# hhv-dcdarknet-varient-1.net
KiCad netlist of a schematic drawn in EAGLE
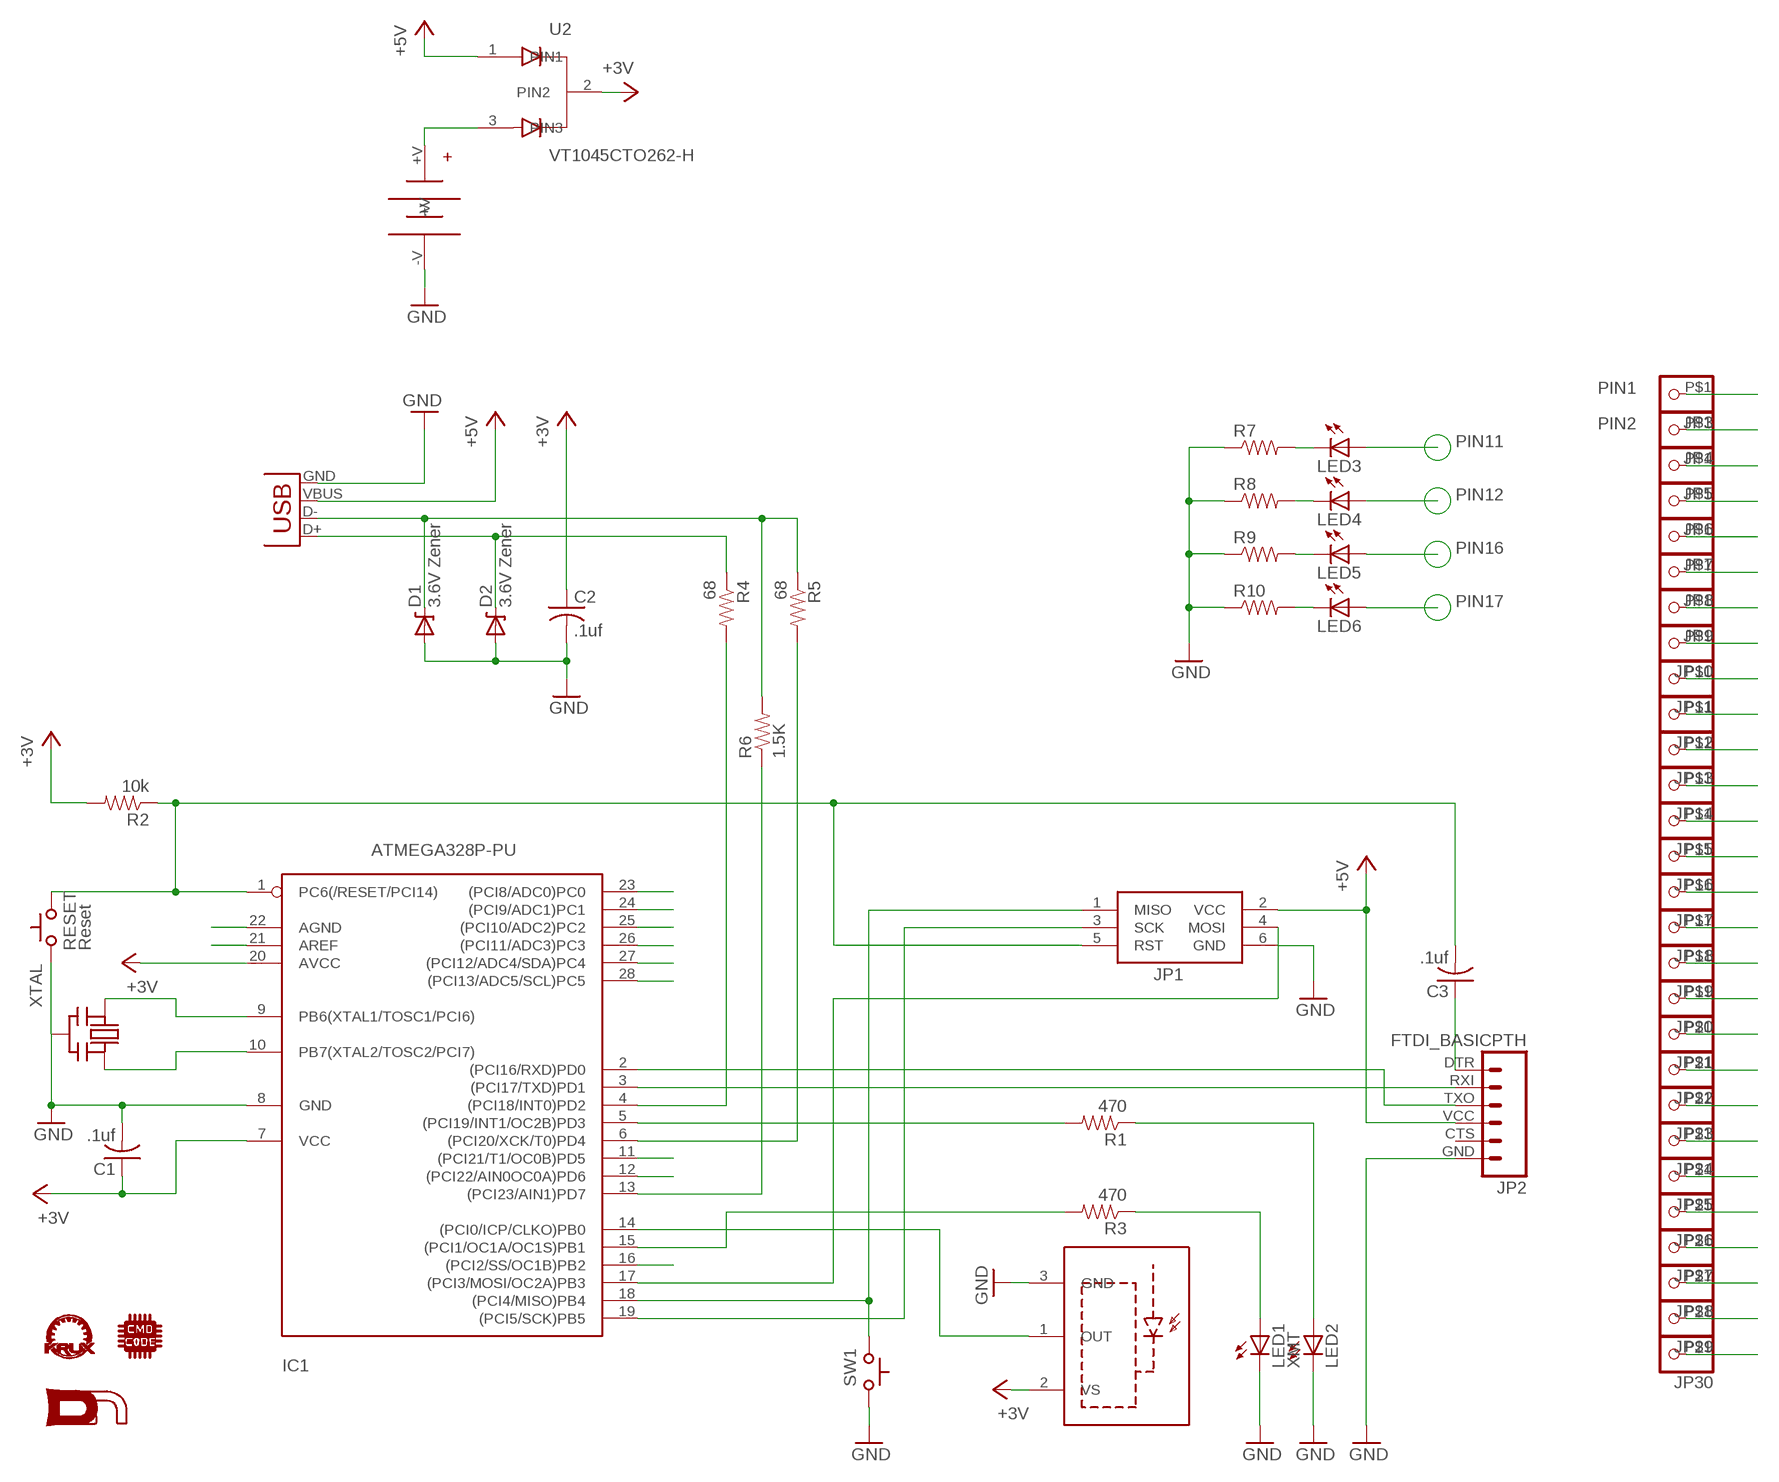
[diagram p0: schematic, sheet 1]

(export (version "E")
  (design (tool "Eeschema 10.0.6"))
  (components
    (comp (ref "C1")
      (value ".1uf")
      (footprint "eagle-import:C025-030X050")
      (libsource (lib "eagle-import") (part "C-US025-030X050"))
    )
    (comp (ref "C2")
      (value ".1uf")
      (footprint "eagle-import:C025-030X050")
      (libsource (lib "eagle-import") (part "C-US025-030X050"))
    )
    (comp (ref "C3")
      (value ".1uf")
      (footprint "eagle-import:C025-030X050")
      (libsource (lib "eagle-import") (part "C-US025-030X050"))
    )
    (comp (ref "D1")
      (value "3.6V Zener")
      (footprint "eagle-import:DIODE-ZENER")
      (libsource (lib "eagle-import") (part "DIODE-ZENERPTH"))
    )
    (comp (ref "D2")
      (value "3.6V Zener")
      (footprint "eagle-import:DIODE-ZENER")
      (libsource (lib "eagle-import") (part "DIODE-ZENERPTH"))
    )
    (comp (ref "IC1")
      (value "ATMEGA328P-PU")
      (footprint "eagle-import:DIL28-3")
      (libsource (lib "eagle-import") (part "ATMEGA168PV-10"))
    )
    (comp (ref "JP1")
      (value "JP1")
      (footprint "eagle-import:AVRISP")
      (libsource (lib "eagle-import") (part "AVRISP-6"))
    )
    (comp (ref "JP2")
      (value "FTDI_BASICPTH")
      (footprint "eagle-import:FTDI_BASIC")
      (libsource (lib "eagle-import") (part "FTDI_BASICPTH"))
    )
    (comp (ref "JP3")
      (value "PINHD-1X11X1_SQUARE")
      (footprint "eagle-import:1X1-SMALL_CUT")
      (libsource (lib "eagle-import") (part "PINHD-1X11X1_SQUARE"))
    )
    (comp (ref "JP4")
      (value "PINHD-1X11X1_SQUARE")
      (footprint "eagle-import:1X1-SMALL_CUT")
      (libsource (lib "eagle-import") (part "PINHD-1X11X1_SQUARE"))
    )
    (comp (ref "JP5")
      (value "PINHD-1X11X1_SQUARE")
      (footprint "eagle-import:1X1-SMALL_CUT")
      (libsource (lib "eagle-import") (part "PINHD-1X11X1_SQUARE"))
    )
    (comp (ref "JP6")
      (value "PINHD-1X11X1_SQUARE")
      (footprint "eagle-import:1X1-SMALL_CUT")
      (libsource (lib "eagle-import") (part "PINHD-1X11X1_SQUARE"))
    )
    (comp (ref "JP7")
      (value "PINHD-1X11X1_SQUARE")
      (footprint "eagle-import:1X1-SMALL_CUT")
      (libsource (lib "eagle-import") (part "PINHD-1X11X1_SQUARE"))
    )
    (comp (ref "JP8")
      (value "PINHD-1X11X1_SQUARE")
      (footprint "eagle-import:1X1-SMALL_CUT")
      (libsource (lib "eagle-import") (part "PINHD-1X11X1_SQUARE"))
    )
    (comp (ref "JP9")
      (value "PINHD-1X11X1_SQUARE")
      (footprint "eagle-import:1X1-SMALL_CUT")
      (libsource (lib "eagle-import") (part "PINHD-1X11X1_SQUARE"))
    )
    (comp (ref "JP10")
      (value "PINHD-1X11X1_SQUARE")
      (footprint "eagle-import:1X1-SMALL_CUT")
      (libsource (lib "eagle-import") (part "PINHD-1X11X1_SQUARE"))
    )
    (comp (ref "JP11")
      (value "PINHD-1X11X1_SQUARE")
      (footprint "eagle-import:1X1-SMALL_CUT")
      (libsource (lib "eagle-import") (part "PINHD-1X11X1_SQUARE"))
    )
    (comp (ref "JP12")
      (value "PINHD-1X11X1_SQUARE")
      (footprint "eagle-import:1X1-SMALL_CUT")
      (libsource (lib "eagle-import") (part "PINHD-1X11X1_SQUARE"))
    )
    (comp (ref "JP13")
      (value "PINHD-1X11X1_SQUARE")
      (footprint "eagle-import:1X1-SMALL_CUT")
      (libsource (lib "eagle-import") (part "PINHD-1X11X1_SQUARE"))
    )
    (comp (ref "JP14")
      (value "PINHD-1X11X1_SQUARE")
      (footprint "eagle-import:1X1-SMALL_CUT")
      (libsource (lib "eagle-import") (part "PINHD-1X11X1_SQUARE"))
    )
    (comp (ref "JP15")
      (value "PINHD-1X11X1_SQUARE")
      (footprint "eagle-import:1X1-SMALL_CUT")
      (libsource (lib "eagle-import") (part "PINHD-1X11X1_SQUARE"))
    )
    (comp (ref "JP16")
      (value "PINHD-1X11X1_SQUARE")
      (footprint "eagle-import:1X1-SMALL_CUT")
      (libsource (lib "eagle-import") (part "PINHD-1X11X1_SQUARE"))
    )
    (comp (ref "JP17")
      (value "PINHD-1X11X1_SQUARE")
      (footprint "eagle-import:1X1-SMALL_CUT")
      (libsource (lib "eagle-import") (part "PINHD-1X11X1_SQUARE"))
    )
    (comp (ref "JP18")
      (value "PINHD-1X11X1_SQUARE")
      (footprint "eagle-import:1X1-SMALL_CUT")
      (libsource (lib "eagle-import") (part "PINHD-1X11X1_SQUARE"))
    )
    (comp (ref "JP19")
      (value "PINHD-1X11X1_SQUARE")
      (footprint "eagle-import:1X1-SMALL_CUT")
      (libsource (lib "eagle-import") (part "PINHD-1X11X1_SQUARE"))
    )
    (comp (ref "JP20")
      (value "PINHD-1X11X1_SQUARE")
      (footprint "eagle-import:1X1-SMALL_CUT")
      (libsource (lib "eagle-import") (part "PINHD-1X11X1_SQUARE"))
    )
    (comp (ref "JP21")
      (value "PINHD-1X11X1_SQUARE")
      (footprint "eagle-import:1X1-SMALL_CUT")
      (libsource (lib "eagle-import") (part "PINHD-1X11X1_SQUARE"))
    )
    (comp (ref "JP22")
      (value "PINHD-1X11X1_SQUARE")
      (footprint "eagle-import:1X1-SMALL_CUT")
      (libsource (lib "eagle-import") (part "PINHD-1X11X1_SQUARE"))
    )
    (comp (ref "JP23")
      (value "PINHD-1X11X1_SQUARE")
      (footprint "eagle-import:1X1-SMALL_CUT")
      (libsource (lib "eagle-import") (part "PINHD-1X11X1_SQUARE"))
    )
    (comp (ref "JP24")
      (value "PINHD-1X11X1_SQUARE")
      (footprint "eagle-import:1X1-SMALL_CUT")
      (libsource (lib "eagle-import") (part "PINHD-1X11X1_SQUARE"))
    )
    (comp (ref "JP25")
      (value "PINHD-1X11X1_SQUARE")
      (footprint "eagle-import:1X1-SMALL_CUT")
      (libsource (lib "eagle-import") (part "PINHD-1X11X1_SQUARE"))
    )
    (comp (ref "JP26")
      (value "PINHD-1X11X1_SQUARE")
      (footprint "eagle-import:1X1-SMALL_CUT")
      (libsource (lib "eagle-import") (part "PINHD-1X11X1_SQUARE"))
    )
    (comp (ref "JP27")
      (value "PINHD-1X11X1_SQUARE")
      (footprint "eagle-import:1X1-SMALL_CUT")
      (libsource (lib "eagle-import") (part "PINHD-1X11X1_SQUARE"))
    )
    (comp (ref "JP28")
      (value "PINHD-1X11X1_SQUARE")
      (footprint "eagle-import:1X1-SMALL_CUT")
      (libsource (lib "eagle-import") (part "PINHD-1X11X1_SQUARE"))
    )
    (comp (ref "JP29")
      (value "PINHD-1X11X1-SMALL")
      (footprint "eagle-import:1X1-SMALL")
      (libsource (lib "eagle-import") (part "PINHD-1X11X1-SMALL"))
    )
    (comp (ref "JP30")
      (value "PINHD-1X11X1-SMALL")
      (footprint "eagle-import:1X1-SMALL")
      (libsource (lib "eagle-import") (part "PINHD-1X11X1-SMALL"))
    )
    (comp (ref "LED1")
      (value "XMT")
      (footprint "eagle-import:LED5MM-FLAT")
      (libsource (lib "eagle-import") (part "LED5MM-FLAT"))
    )
    (comp (ref "LED2")
      (value "LED5MM-FLAT")
      (footprint "eagle-import:LED5MM-FLAT")
      (libsource (lib "eagle-import") (part "LED5MM-FLAT"))
    )
    (comp (ref "LED3")
      (value "LED1206")
      (footprint "eagle-import:LED-1206")
      (libsource (lib "eagle-import") (part "SparkFun_LED1206"))
    )
    (comp (ref "LED4")
      (value "LED1206")
      (footprint "eagle-import:LED-1206")
      (libsource (lib "eagle-import") (part "SparkFun_LED1206"))
    )
    (comp (ref "LED5")
      (value "LED1206")
      (footprint "eagle-import:LED-1206")
      (libsource (lib "eagle-import") (part "SparkFun_LED1206"))
    )
    (comp (ref "LED6")
      (value "LED1206")
      (footprint "eagle-import:LED-1206")
      (libsource (lib "eagle-import") (part "SparkFun_LED1206"))
    )
    (comp (ref "R1")
      (value "470")
      (footprint "eagle-import:AXIAL-0.3")
      (libsource (lib "eagle-import") (part "RESISTORAXIAL-0.3"))
    )
    (comp (ref "R2")
      (value "10k")
      (footprint "eagle-import:AXIAL-0.3")
      (libsource (lib "eagle-import") (part "RESISTORAXIAL-0.3"))
    )
    (comp (ref "R3")
      (value "470")
      (footprint "eagle-import:AXIAL-0.3")
      (libsource (lib "eagle-import") (part "RESISTORAXIAL-0.3"))
    )
    (comp (ref "R4")
      (value "68")
      (footprint "eagle-import:AXIAL-0.3")
      (libsource (lib "eagle-import") (part "RESISTORAXIAL-0.3"))
    )
    (comp (ref "R5")
      (value "68")
      (footprint "eagle-import:AXIAL-0.3")
      (libsource (lib "eagle-import") (part "RESISTORAXIAL-0.3"))
    )
    (comp (ref "R6")
      (value "1.5K")
      (footprint "eagle-import:AXIAL-0.3")
      (libsource (lib "eagle-import") (part "RESISTORAXIAL-0.3"))
    )
    (comp (ref "R7")
      (value "RESISTOR1206")
      (footprint "eagle-import:1206")
      (libsource (lib "eagle-import") (part "SparkFun_RESISTOR1206"))
    )
    (comp (ref "R8")
      (value "RESISTOR1206")
      (footprint "eagle-import:1206")
      (libsource (lib "eagle-import") (part "SparkFun_RESISTOR1206"))
    )
    (comp (ref "R9")
      (value "RESISTOR1206")
      (footprint "eagle-import:1206")
      (libsource (lib "eagle-import") (part "SparkFun_RESISTOR1206"))
    )
    (comp (ref "R10")
      (value "RESISTOR1206")
      (footprint "eagle-import:1206")
      (libsource (lib "eagle-import") (part "SparkFun_RESISTOR1206"))
    )
    (comp (ref "RESET")
      (value "Reset")
      (footprint "eagle-import:TACTILE-2PIN")
      (libsource (lib "eagle-import") (part "SWITCH_TACTILETACTILE-2PIN"))
    )
    (comp (ref "SW1")
      (value "SWITCH_TACTILETACTILE-2PIN")
      (footprint "eagle-import:TACTILE-2PIN")
      (libsource (lib "eagle-import") (part "SWITCH_TACTILETACTILE-2PIN"))
    )
    (comp (ref "U$1")
      (value "DN_LOGO")
      (footprint "eagle-import:DN_LOGO")
      (libsource (lib "eagle-import") (part "DN_LOGO"))
    )
    (comp (ref "U$2")
      (value "CMDC0DE_LOGO")
      (footprint "eagle-import:CMDC0DE")
      (libsource (lib "eagle-import") (part "CMDC0DE_LOGO"))
    )
    (comp (ref "U$3")
      (value "KRUX_LOGO")
      (footprint "eagle-import:KRUX_LOGO")
      (libsource (lib "eagle-import") (part "KRUX_LOGO"))
    )
    (comp (ref "U$5")
      (value "12BH423-GR3-CELL_NOBORDER")
      (footprint "eagle-import:3-AAA-CELL_NOBORDER")
      (libsource (lib "eagle-import") (part "12BH423-GR3-CELL_NOBORDER"))
    )
    (comp (ref "U1")
      (value "RCV")
      (footprint "eagle-import:IR-MODULE")
      (libsource (lib "eagle-import") (part "SOP22"))
    )
    (comp (ref "U2")
      (value "VT1045CTO262-H")
      (footprint "eagle-import:TO262-H")
      (libsource (lib "eagle-import") (part "VT1045CTO262-H"))
    )
    (comp (ref "X2")
      (value "USB")
      (footprint "eagle-import:USB-B-PTH")
      (libsource (lib "eagle-import") (part "USBPTH"))
    )
    (comp (ref "XTAL")
      (value "CERMOSCILL-THM")
      (footprint "eagle-import:CERM_OSC")
      (libsource (lib "eagle-import") (part "CERMOSCILL-THM"))
    )
  )
  (nets
    (net (code "1") (name "+3V") (class "Default")
      (node (ref "C1") (pin "1") (pinfunction "1_1") (pintype "passive"))
      (node (ref "C2") (pin "1") (pinfunction "1_1") (pintype "passive"))
      (node (ref "IC1") (pin "20") (pinfunction "AVCC_20") (pintype "bidirectional"))
      (node (ref "IC1") (pin "7") (pinfunction "VCC_7") (pintype "bidirectional"))
      (node (ref "JP22") (pin "P$1") (pinfunction "1_P$1") (pintype "passive"))
      (node (ref "JP9") (pin "P$1") (pinfunction "1_P$1") (pintype "passive"))
      (node (ref "R2") (pin "P$2") (pinfunction "2_P$2") (pintype "passive"))
      (node (ref "U1") (pin "2") (pinfunction "VS_2") (pintype "bidirectional"))
      (node (ref "U2") (pin "2") (pinfunction "PIN2_2") (pintype "bidirectional"))
    )
    (net (code "2") (name "+5V") (class "Default")
      (node (ref "JP1") (pin "2") (pinfunction "VCC_2") (pintype "power_in"))
      (node (ref "JP2") (pin "VCC") (pinfunction "4_VCC") (pintype "passive"))
      (node (ref "U2") (pin "1") (pinfunction "PIN1_1") (pintype "bidirectional"))
      (node (ref "X2") (pin "VBUS") (pinfunction "VBUS_VBUS") (pintype "bidirectional"))
    )
    (net (code "3") (name "/PIN1") (class "Default")
      (node (ref "C3") (pin "2") (pinfunction "2_2") (pintype "passive"))
      (node (ref "IC1") (pin "1") (pinfunction "PC6(/RESET/PCI14)_1") (pintype "bidirectional"))
      (node (ref "JP1") (pin "5") (pinfunction "RST_5") (pintype "output"))
      (node (ref "JP3") (pin "P$1") (pinfunction "1_P$1") (pintype "passive"))
      (node (ref "R2") (pin "P$1") (pinfunction "1_P$1") (pintype "passive"))
      (node (ref "RESET") (pin "P$1") (pinfunction "A_P$1") (pintype "passive"))
    )
    (net (code "4") (name "/PIN2") (class "Default")
      (node (ref "IC1") (pin "2") (pinfunction "(PCI16/RXD)PD0_2") (pintype "bidirectional"))
      (node (ref "JP2") (pin "TXO") (pinfunction "3_TXO") (pintype "passive"))
      (node (ref "JP4") (pin "P$1") (pinfunction "1_P$1") (pintype "passive"))
    )
    (net (code "5") (name "/PIN3") (class "Default")
      (node (ref "IC1") (pin "3") (pinfunction "(PCI17/TXD)PD1_3") (pintype "bidirectional"))
      (node (ref "JP2") (pin "RXI") (pinfunction "2_RXI") (pintype "passive"))
      (node (ref "JP5") (pin "P$1") (pinfunction "1_P$1") (pintype "passive"))
    )
    (net (code "6") (name "/PIN4") (class "Default")
      (node (ref "IC1") (pin "4") (pinfunction "(PCI18/INT0)PD2_4") (pintype "bidirectional"))
      (node (ref "JP6") (pin "P$1") (pinfunction "1_P$1") (pintype "passive"))
      (node (ref "R4") (pin "P$2") (pinfunction "2_P$2") (pintype "passive"))
    )
    (net (code "7") (name "/PIN5") (class "Default")
      (node (ref "IC1") (pin "5") (pinfunction "(PCI19/INT1/OC2B)PD3_5") (pintype "bidirectional"))
      (node (ref "JP7") (pin "P$1") (pinfunction "1_P$1") (pintype "passive"))
      (node (ref "R1") (pin "P$2") (pinfunction "2_P$2") (pintype "passive"))
    )
    (net (code "8") (name "/PIN6") (class "Default")
      (node (ref "IC1") (pin "6") (pinfunction "(PCI20/XCK/T0)PD4_6") (pintype "bidirectional"))
      (node (ref "JP8") (pin "P$1") (pinfunction "1_P$1") (pintype "passive"))
      (node (ref "R5") (pin "P$2") (pinfunction "2_P$2") (pintype "passive"))
    )
    (net (code "9") (name "/PIN9") (class "Default")
      (node (ref "IC1") (pin "9") (pinfunction "PB6(XTAL1/TOSC1/PCI6)_9") (pintype "bidirectional"))
      (node (ref "JP11") (pin "P$1") (pinfunction "1_P$1") (pintype "passive"))
      (node (ref "XTAL") (pin "P$1") (pinfunction "IN_P$1") (pintype "bidirectional"))
    )
    (net (code "10") (name "/PIN10") (class "Default")
      (node (ref "IC1") (pin "10") (pinfunction "PB7(XTAL2/TOSC2/PCI7)_10") (pintype "bidirectional"))
      (node (ref "JP12") (pin "P$1") (pinfunction "1_P$1") (pintype "passive"))
      (node (ref "XTAL") (pin "P$3") (pinfunction "OUT_P$3") (pintype "bidirectional"))
    )
    (net (code "11") (name "/PIN11") (class "Default")
      (node (ref "IC1") (pin "11") (pinfunction "(PCI21/T1/OC0B)PD5_11") (pintype "bidirectional"))
      (node (ref "JP13") (pin "P$1") (pinfunction "1_P$1") (pintype "passive"))
      (node (ref "LED3") (pin "A") (pinfunction "A_A") (pintype "passive"))
    )
    (net (code "12") (name "/PIN12") (class "Default")
      (node (ref "IC1") (pin "12") (pinfunction "(PCI22/AIN0OC0A)PD6_12") (pintype "bidirectional"))
      (node (ref "JP14") (pin "P$1") (pinfunction "1_P$1") (pintype "passive"))
      (node (ref "LED4") (pin "A") (pinfunction "A_A") (pintype "passive"))
    )
    (net (code "13") (name "/PIN13") (class "Default")
      (node (ref "IC1") (pin "13") (pinfunction "(PCI23/AIN1)PD7_13") (pintype "bidirectional"))
      (node (ref "JP15") (pin "P$1") (pinfunction "1_P$1") (pintype "passive"))
      (node (ref "R6") (pin "P$1") (pinfunction "1_P$1") (pintype "passive"))
    )
    (net (code "14") (name "/PIN14") (class "Default")
      (node (ref "IC1") (pin "14") (pinfunction "(PCI0/ICP/CLKO)PB0_14") (pintype "bidirectional"))
      (node (ref "JP16") (pin "P$1") (pinfunction "1_P$1") (pintype "passive"))
      (node (ref "U1") (pin "1") (pinfunction "OUT_1") (pintype "bidirectional"))
    )
    (net (code "15") (name "/PIN15") (class "Default")
      (node (ref "IC1") (pin "15") (pinfunction "(PCI1/OC1A/OC1S)PB1_15") (pintype "bidirectional"))
      (node (ref "JP17") (pin "P$1") (pinfunction "1_P$1") (pintype "passive"))
      (node (ref "R3") (pin "P$2") (pinfunction "2_P$2") (pintype "passive"))
    )
    (net (code "16") (name "/PIN16") (class "Default")
      (node (ref "IC1") (pin "16") (pinfunction "(PCI2/SS/OC1B)PB2_16") (pintype "bidirectional"))
      (node (ref "JP18") (pin "P$1") (pinfunction "1_P$1") (pintype "passive"))
      (node (ref "LED5") (pin "A") (pinfunction "A_A") (pintype "passive"))
    )
    (net (code "17") (name "/PIN17") (class "Default")
      (node (ref "IC1") (pin "17") (pinfunction "(PCI3/MOSI/OC2A)PB3_17") (pintype "bidirectional"))
      (node (ref "JP1") (pin "4") (pinfunction "MOSI_4") (pintype "output"))
      (node (ref "JP19") (pin "P$1") (pinfunction "1_P$1") (pintype "passive"))
      (node (ref "LED6") (pin "A") (pinfunction "A_A") (pintype "passive"))
    )
    (net (code "18") (name "/PIN18") (class "Default")
      (node (ref "IC1") (pin "18") (pinfunction "(PCI4/MISO)PB4_18") (pintype "bidirectional"))
      (node (ref "JP1") (pin "1") (pinfunction "MISO_1") (pintype "input"))
      (node (ref "JP20") (pin "P$1") (pinfunction "1_P$1") (pintype "passive"))
      (node (ref "SW1") (pin "P$2") (pinfunction "C_P$2") (pintype "passive"))
    )
    (net (code "19") (name "/PIN19") (class "Default")
      (node (ref "IC1") (pin "19") (pinfunction "(PCI5/SCK)PB5_19") (pintype "bidirectional"))
      (node (ref "JP1") (pin "3") (pinfunction "SCK_3") (pintype "output"))
      (node (ref "JP21") (pin "P$1") (pinfunction "1_P$1") (pintype "passive"))
    )
    (net (code "20") (name "/PIN21") (class "Default")
      (node (ref "IC1") (pin "21") (pinfunction "AREF_21") (pintype "bidirectional"))
      (node (ref "JP23") (pin "P$1") (pinfunction "1_P$1") (pintype "passive"))
    )
    (net (code "21") (name "/PIN22") (class "Default")
      (node (ref "IC1") (pin "22") (pinfunction "AGND_22") (pintype "bidirectional"))
      (node (ref "JP24") (pin "P$1") (pinfunction "1_P$1") (pintype "passive"))
    )
    (net (code "22") (name "/PIN23") (class "Default")
      (node (ref "IC1") (pin "23") (pinfunction "(PCI8/ADC0)PC0_23") (pintype "bidirectional"))
      (node (ref "JP25") (pin "P$1") (pinfunction "1_P$1") (pintype "passive"))
    )
    (net (code "23") (name "/PIN24") (class "Default")
      (node (ref "IC1") (pin "24") (pinfunction "(PCI9/ADC1)PC1_24") (pintype "bidirectional"))
      (node (ref "JP26") (pin "P$1") (pinfunction "1_P$1") (pintype "passive"))
    )
    (net (code "24") (name "/PIN25") (class "Default")
      (node (ref "IC1") (pin "25") (pinfunction "(PCI10/ADC2)PC2_25") (pintype "bidirectional"))
      (node (ref "JP27") (pin "P$1") (pinfunction "1_P$1") (pintype "passive"))
    )
    (net (code "25") (name "/PIN26") (class "Default")
      (node (ref "IC1") (pin "26") (pinfunction "(PCI11/ADC3)PC3_26") (pintype "bidirectional"))
      (node (ref "JP28") (pin "P$1") (pinfunction "1_P$1") (pintype "passive"))
    )
    (net (code "26") (name "/PIN27") (class "Default")
      (node (ref "IC1") (pin "27") (pinfunction "(PCI12/ADC4/SDA)PC4_27") (pintype "bidirectional"))
      (node (ref "JP29") (pin "P$1") (pinfunction "1_P$1") (pintype "passive"))
    )
    (net (code "27") (name "/PIN28") (class "Default")
      (node (ref "IC1") (pin "28") (pinfunction "(PCI13/ADC5/SCL)PC5_28") (pintype "bidirectional"))
      (node (ref "JP30") (pin "P$1") (pinfunction "1_P$1") (pintype "passive"))
    )
    (net (code "28") (name "GND") (class "Default")
      (node (ref "C1") (pin "2") (pinfunction "2_2") (pintype "passive"))
      (node (ref "C2") (pin "2") (pinfunction "2_2") (pintype "passive"))
      (node (ref "D1") (pin "P$2") (pinfunction "A_P$2") (pintype "passive"))
      (node (ref "D2") (pin "P$2") (pinfunction "A_P$2") (pintype "passive"))
      (node (ref "IC1") (pin "8") (pinfunction "GND_8") (pintype "bidirectional"))
      (node (ref "JP1") (pin "6") (pinfunction "GND_6") (pintype "power_in"))
      (node (ref "JP10") (pin "P$1") (pinfunction "1_P$1") (pintype "passive"))
      (node (ref "JP2") (pin "GND") (pinfunction "6_GND") (pintype "passive"))
      (node (ref "LED1") (pin "K") (pinfunction "C_K") (pintype "passive"))
      (node (ref "LED2") (pin "K") (pinfunction "C_K") (pintype "passive"))
      (node (ref "R10") (pin "1") (pinfunction "1_1") (pintype "passive"))
      (node (ref "R7") (pin "1") (pinfunction "1_1") (pintype "passive"))
      (node (ref "R8") (pin "1") (pinfunction "1_1") (pintype "passive"))
      (node (ref "R9") (pin "1") (pinfunction "1_1") (pintype "passive"))
      (node (ref "RESET") (pin "P$2") (pinfunction "C_P$2") (pintype "passive"))
      (node (ref "SW1") (pin "P$1") (pinfunction "A_P$1") (pintype "passive"))
      (node (ref "U$5") (pin "-V") (pinfunction "-V_-V") (pintype "bidirectional"))
      (node (ref "U1") (pin "3") (pinfunction "GND_3") (pintype "bidirectional"))
      (node (ref "X2") (pin "GND") (pinfunction "GND_GND") (pintype "bidirectional"))
      (node (ref "XTAL") (pin "P$2") (pinfunction "GND_P$2") (pintype "bidirectional"))
    )
    (net (code "29") (name "Net-(D1-C)") (class "Default")
      (node (ref "D1") (pin "P$1") (pinfunction "C_P$1") (pintype "passive"))
      (node (ref "R5") (pin "P$1") (pinfunction "1_P$1") (pintype "passive"))
      (node (ref "R6") (pin "P$2") (pinfunction "2_P$2") (pintype "passive"))
      (node (ref "X2") (pin "D-") (pinfunction "D-_D-") (pintype "bidirectional"))
    )
    (net (code "30") (name "Net-(D2-C)") (class "Default")
      (node (ref "D2") (pin "P$1") (pinfunction "C_P$1") (pintype "passive"))
      (node (ref "R4") (pin "P$1") (pinfunction "1_P$1") (pintype "passive"))
      (node (ref "X2") (pin "D+") (pinfunction "D+_D+") (pintype "bidirectional"))
    )
    (net (code "31") (name "Net-(JP2-1)") (class "Default")
      (node (ref "C3") (pin "1") (pinfunction "1_1") (pintype "passive"))
      (node (ref "JP2") (pin "DTR") (pinfunction "1_DTR") (pintype "passive"))
    )
    (net (code "32") (name "Net-(LED3-PadC)") (class "Default")
      (node (ref "LED3") (pin "C") (pinfunction "C_C") (pintype "passive"))
      (node (ref "R7") (pin "2") (pinfunction "2_2") (pintype "passive"))
    )
    (net (code "33") (name "Net-(LED4-PadC)") (class "Default")
      (node (ref "LED4") (pin "C") (pinfunction "C_C") (pintype "passive"))
      (node (ref "R8") (pin "2") (pinfunction "2_2") (pintype "passive"))
    )
    (net (code "34") (name "Net-(LED5-PadC)") (class "Default")
      (node (ref "LED5") (pin "C") (pinfunction "C_C") (pintype "passive"))
      (node (ref "R9") (pin "2") (pinfunction "2_2") (pintype "passive"))
    )
    (net (code "35") (name "Net-(LED6-PadC)") (class "Default")
      (node (ref "LED6") (pin "C") (pinfunction "C_C") (pintype "passive"))
      (node (ref "R10") (pin "2") (pinfunction "2_2") (pintype "passive"))
    )
    (net (code "36") (name "Net-(R1-1)") (class "Default")
      (node (ref "LED2") (pin "A") (pinfunction "A_A") (pintype "passive"))
      (node (ref "R1") (pin "P$1") (pinfunction "1_P$1") (pintype "passive"))
    )
    (net (code "37") (name "Net-(R3-1)") (class "Default")
      (node (ref "LED1") (pin "A") (pinfunction "A_A") (pintype "passive"))
      (node (ref "R3") (pin "P$1") (pinfunction "1_P$1") (pintype "passive"))
    )
    (net (code "38") (name "Net-(U2-PIN3)") (class "Default")
      (node (ref "U$5") (pin "+V") (pinfunction "+V_+V") (pintype "bidirectional"))
      (node (ref "U2") (pin "3") (pinfunction "PIN3_3") (pintype "bidirectional"))
    )
    (net (code "39") (name "unconnected-(JP2-5-PadCTS)") (class "Default")
      (node (ref "JP2") (pin "CTS") (pinfunction "5_CTS") (pintype "passive"))
    )
  )
)
